# pwm-logger.net
KiCad netlist of a schematic drawn in EAGLE
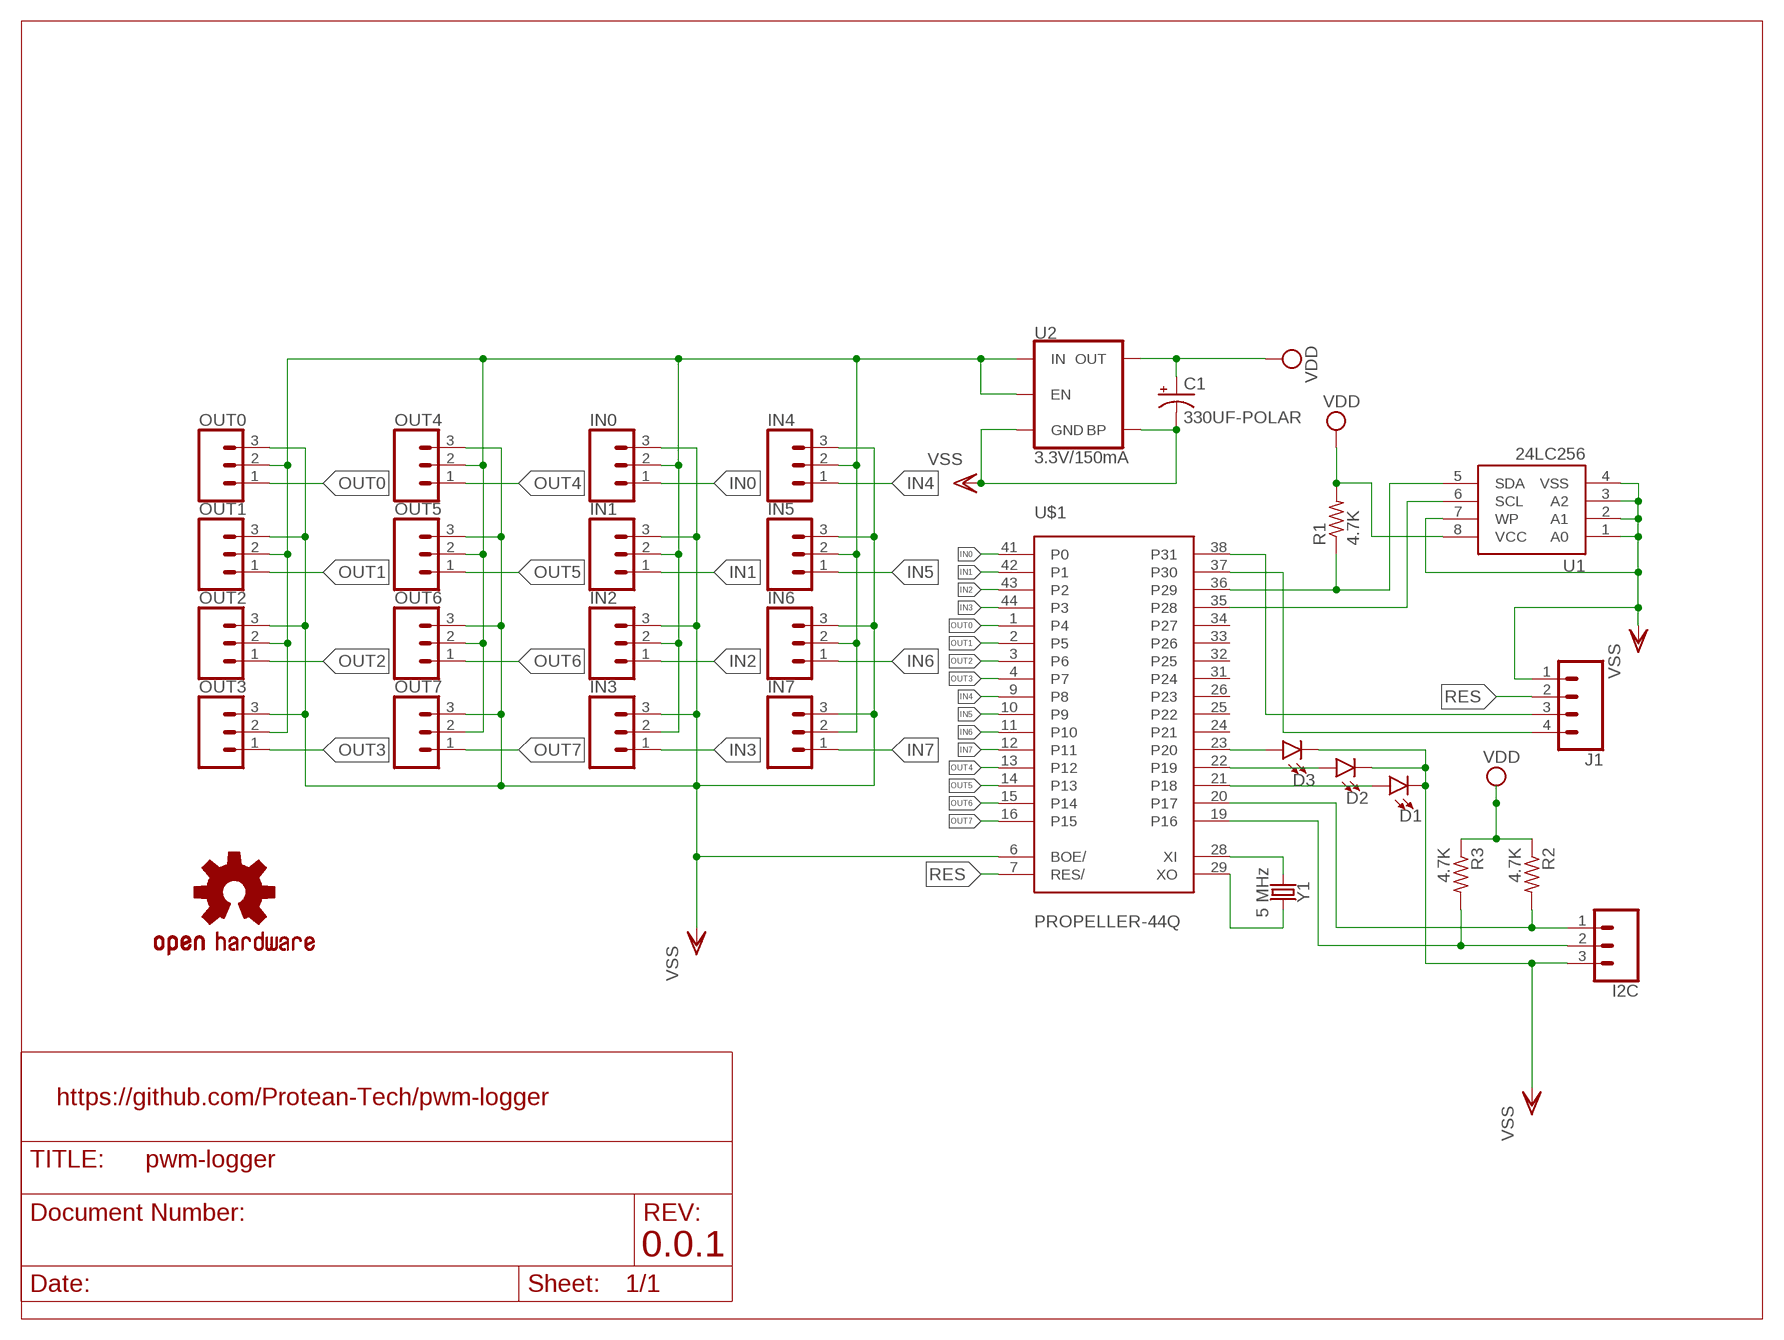
[diagram p0: schematic, sheet 1]

(export (version "E")
  (design (tool "Eeschema 10.0.6"))
  (components
    (comp (ref "C1")
      (value "330UF-POLAR")
      (footprint "eagle-import:1311")
      (libsource (lib "eagle-import") (part "330UF-POLAR"))
    )
    (comp (ref "D1")
      (value "LED-FKIT-1206")
      (footprint "eagle-import:FKIT-LED-1206")
      (libsource (lib "eagle-import") (part "LED-FKIT-1206"))
    )
    (comp (ref "D2")
      (value "LED-FKIT-1206")
      (footprint "eagle-import:FKIT-LED-1206")
      (libsource (lib "eagle-import") (part "LED-FKIT-1206"))
    )
    (comp (ref "D3")
      (value "LED-FKIT-1206")
      (footprint "eagle-import:FKIT-LED-1206")
      (libsource (lib "eagle-import") (part "LED-FKIT-1206"))
    )
    (comp (ref "I2C")
      (value "CONN_03")
      (footprint "eagle-import:1X03")
      (libsource (lib "eagle-import") (part "CONN_03"))
    )
    (comp (ref "IN0")
      (value "CONN_03")
      (footprint "eagle-import:1X03")
      (libsource (lib "eagle-import") (part "CONN_03"))
    )
    (comp (ref "IN1")
      (value "CONN_03")
      (footprint "eagle-import:1X03")
      (libsource (lib "eagle-import") (part "CONN_03"))
    )
    (comp (ref "IN2")
      (value "CONN_03")
      (footprint "eagle-import:1X03")
      (libsource (lib "eagle-import") (part "CONN_03"))
    )
    (comp (ref "IN3")
      (value "CONN_03")
      (footprint "eagle-import:1X03")
      (libsource (lib "eagle-import") (part "CONN_03"))
    )
    (comp (ref "IN4")
      (value "CONN_03")
      (footprint "eagle-import:1X03")
      (libsource (lib "eagle-import") (part "CONN_03"))
    )
    (comp (ref "IN5")
      (value "CONN_03")
      (footprint "eagle-import:1X03")
      (libsource (lib "eagle-import") (part "CONN_03"))
    )
    (comp (ref "IN6")
      (value "CONN_03")
      (footprint "eagle-import:1X03")
      (libsource (lib "eagle-import") (part "CONN_03"))
    )
    (comp (ref "IN7")
      (value "CONN_03")
      (footprint "eagle-import:1X03")
      (libsource (lib "eagle-import") (part "CONN_03"))
    )
    (comp (ref "J1")
      (value "CONN_04")
      (footprint "eagle-import:1X04")
      (libsource (lib "eagle-import") (part "CONN_04"))
    )
    (comp (ref "LOGO1")
      (value "OSHW-LOGOM")
      (footprint "eagle-import:OSHW-LOGO-M")
      (libsource (lib "eagle-import") (part "OSHW-LOGOM"))
    )
    (comp (ref "OUT0")
      (value "CONN_03")
      (footprint "eagle-import:1X03")
      (libsource (lib "eagle-import") (part "CONN_03"))
    )
    (comp (ref "OUT1")
      (value "CONN_03")
      (footprint "eagle-import:1X03")
      (libsource (lib "eagle-import") (part "CONN_03"))
    )
    (comp (ref "OUT2")
      (value "CONN_03")
      (footprint "eagle-import:1X03")
      (libsource (lib "eagle-import") (part "CONN_03"))
    )
    (comp (ref "OUT3")
      (value "CONN_03")
      (footprint "eagle-import:1X03")
      (libsource (lib "eagle-import") (part "CONN_03"))
    )
    (comp (ref "OUT4")
      (value "CONN_03")
      (footprint "eagle-import:1X03")
      (libsource (lib "eagle-import") (part "CONN_03"))
    )
    (comp (ref "OUT5")
      (value "CONN_03")
      (footprint "eagle-import:1X03")
      (libsource (lib "eagle-import") (part "CONN_03"))
    )
    (comp (ref "OUT6")
      (value "CONN_03")
      (footprint "eagle-import:1X03")
      (libsource (lib "eagle-import") (part "CONN_03"))
    )
    (comp (ref "OUT7")
      (value "CONN_03")
      (footprint "eagle-import:1X03")
      (libsource (lib "eagle-import") (part "CONN_03"))
    )
    (comp (ref "R1")
      (value "4.7K")
      (footprint "eagle-import:M2012")
      (libsource (lib "eagle-import") (part "R-US_M2012"))
    )
    (comp (ref "R2")
      (value "4.7K")
      (footprint "eagle-import:M2012")
      (libsource (lib "eagle-import") (part "R-US_M2012"))
    )
    (comp (ref "R3")
      (value "4.7K")
      (footprint "eagle-import:M2012")
      (libsource (lib "eagle-import") (part "R-US_M2012"))
    )
    (comp (ref "U$1")
      (value "PROPELLER-44Q")
      (footprint "eagle-import:Q44")
      (libsource (lib "eagle-import") (part "PROPELLER-44Q"))
    )
    (comp (ref "U1")
      (value "24LC256")
      (footprint "eagle-import:SO08")
      (libsource (lib "eagle-import") (part "EEPROM-I2CSMD"))
    )
    (comp (ref "U2")
      (value "3.3V/150mA")
      (footprint "eagle-import:SOT23-5")
      (libsource (lib "eagle-import") (part "V_REG_MIC52053.3V"))
    )
    (comp (ref "Y1")
      (value "5 MHz")
      (footprint "eagle-import:HC49U")
      (libsource (lib "eagle-import") (part "CRYSTALPTH-HC49UV"))
    )
  )
  (nets
    (net (code "1") (name "IN0") (class "Default")
      (node (ref "IN0") (pin "1") (pinfunction "1_1") (pintype "passive"))
      (node (ref "U$1") (pin "41") (pinfunction "P0_41") (pintype "bidirectional"))
    )
    (net (code "2") (name "IN1") (class "Default")
      (node (ref "IN1") (pin "1") (pinfunction "1_1") (pintype "passive"))
      (node (ref "U$1") (pin "42") (pinfunction "P1_42") (pintype "bidirectional"))
    )
    (net (code "3") (name "IN2") (class "Default")
      (node (ref "IN2") (pin "1") (pinfunction "1_1") (pintype "passive"))
      (node (ref "U$1") (pin "43") (pinfunction "P2_43") (pintype "bidirectional"))
    )
    (net (code "4") (name "IN3") (class "Default")
      (node (ref "IN3") (pin "1") (pinfunction "1_1") (pintype "passive"))
      (node (ref "U$1") (pin "44") (pinfunction "P3_44") (pintype "bidirectional"))
    )
    (net (code "5") (name "IN4") (class "Default")
      (node (ref "IN4") (pin "1") (pinfunction "1_1") (pintype "passive"))
      (node (ref "U$1") (pin "9") (pinfunction "P8_9") (pintype "bidirectional"))
    )
    (net (code "6") (name "IN5") (class "Default")
      (node (ref "IN5") (pin "1") (pinfunction "1_1") (pintype "passive"))
      (node (ref "U$1") (pin "10") (pinfunction "P9_10") (pintype "bidirectional"))
    )
    (net (code "7") (name "IN6") (class "Default")
      (node (ref "IN6") (pin "1") (pinfunction "1_1") (pintype "passive"))
      (node (ref "U$1") (pin "11") (pinfunction "P10_11") (pintype "bidirectional"))
    )
    (net (code "8") (name "IN7") (class "Default")
      (node (ref "IN7") (pin "1") (pinfunction "1_1") (pintype "passive"))
      (node (ref "U$1") (pin "12") (pinfunction "P11_12") (pintype "bidirectional"))
    )
    (net (code "9") (name "Net-(U$1A-P16)") (class "Default")
      (node (ref "I2C") (pin "2") (pinfunction "2_2") (pintype "passive"))
      (node (ref "R3") (pin "2") (pinfunction "2_2") (pintype "passive"))
      (node (ref "U$1") (pin "19") (pinfunction "P16_19") (pintype "bidirectional"))
    )
    (net (code "10") (name "Net-(U$1A-P17)") (class "Default")
      (node (ref "I2C") (pin "1") (pinfunction "1_1") (pintype "passive"))
      (node (ref "R2") (pin "2") (pinfunction "2_2") (pintype "passive"))
      (node (ref "U$1") (pin "20") (pinfunction "P17_20") (pintype "bidirectional"))
    )
    (net (code "11") (name "Net-(U$1A-P18)") (class "Default")
      (node (ref "D1") (pin "A") (pinfunction "A_A") (pintype "passive"))
      (node (ref "U$1") (pin "21") (pinfunction "P18_21") (pintype "bidirectional"))
    )
    (net (code "12") (name "Net-(U$1A-P19)") (class "Default")
      (node (ref "D2") (pin "A") (pinfunction "A_A") (pintype "passive"))
      (node (ref "U$1") (pin "22") (pinfunction "P19_22") (pintype "bidirectional"))
    )
    (net (code "13") (name "Net-(U$1A-P20)") (class "Default")
      (node (ref "D3") (pin "A") (pinfunction "A_A") (pintype "passive"))
      (node (ref "U$1") (pin "23") (pinfunction "P20_23") (pintype "bidirectional"))
    )
    (net (code "14") (name "Net-(U$1A-P28)") (class "Default")
      (node (ref "U$1") (pin "35") (pinfunction "P28_35") (pintype "bidirectional"))
      (node (ref "U1") (pin "6") (pinfunction "SCL_6") (pintype "bidirectional"))
    )
    (net (code "15") (name "Net-(U$1A-P29)") (class "Default")
      (node (ref "R1") (pin "1") (pinfunction "1_1") (pintype "passive"))
      (node (ref "U$1") (pin "36") (pinfunction "P29_36") (pintype "bidirectional"))
      (node (ref "U1") (pin "5") (pinfunction "SDA_5") (pintype "bidirectional"))
    )
    (net (code "16") (name "Net-(U$1A-P30)") (class "Default")
      (node (ref "J1") (pin "4") (pinfunction "4_4") (pintype "passive"))
      (node (ref "U$1") (pin "37") (pinfunction "P30_37") (pintype "bidirectional"))
    )
    (net (code "17") (name "Net-(U$1A-P31)") (class "Default")
      (node (ref "J1") (pin "3") (pinfunction "3_3") (pintype "passive"))
      (node (ref "U$1") (pin "38") (pinfunction "P31_38") (pintype "bidirectional"))
    )
    (net (code "18") (name "Net-(U$1A-XI)") (class "Default")
      (node (ref "U$1") (pin "28") (pinfunction "XI_28") (pintype "input"))
      (node (ref "Y1") (pin "1") (pinfunction "1_1") (pintype "passive"))
    )
    (net (code "19") (name "Net-(U$1A-XO)") (class "Default")
      (node (ref "U$1") (pin "29") (pinfunction "XO_29") (pintype "output"))
      (node (ref "Y1") (pin "2") (pinfunction "2_2") (pintype "passive"))
    )
    (net (code "20") (name "Net-(U2-EN)") (class "Default")
      (node (ref "IN0") (pin "2") (pinfunction "2_2") (pintype "passive"))
      (node (ref "IN1") (pin "2") (pinfunction "2_2") (pintype "passive"))
      (node (ref "IN2") (pin "2") (pinfunction "2_2") (pintype "passive"))
      (node (ref "IN3") (pin "2") (pinfunction "2_2") (pintype "passive"))
      (node (ref "IN4") (pin "2") (pinfunction "2_2") (pintype "passive"))
      (node (ref "IN5") (pin "2") (pinfunction "2_2") (pintype "passive"))
      (node (ref "IN6") (pin "2") (pinfunction "2_2") (pintype "passive"))
      (node (ref "IN7") (pin "2") (pinfunction "2_2") (pintype "passive"))
      (node (ref "OUT0") (pin "2") (pinfunction "2_2") (pintype "passive"))
      (node (ref "OUT1") (pin "2") (pinfunction "2_2") (pintype "passive"))
      (node (ref "OUT2") (pin "2") (pinfunction "2_2") (pintype "passive"))
      (node (ref "OUT3") (pin "2") (pinfunction "2_2") (pintype "passive"))
      (node (ref "OUT4") (pin "2") (pinfunction "2_2") (pintype "passive"))
      (node (ref "OUT5") (pin "2") (pinfunction "2_2") (pintype "passive"))
      (node (ref "OUT6") (pin "2") (pinfunction "2_2") (pintype "passive"))
      (node (ref "OUT7") (pin "2") (pinfunction "2_2") (pintype "passive"))
      (node (ref "U2") (pin "1") (pinfunction "IN_1") (pintype "input"))
      (node (ref "U2") (pin "3") (pinfunction "EN_3") (pintype "input"))
    )
    (net (code "21") (name "OUT0") (class "Default")
      (node (ref "OUT0") (pin "1") (pinfunction "1_1") (pintype "passive"))
      (node (ref "U$1") (pin "1") (pinfunction "P4_1") (pintype "bidirectional"))
    )
    (net (code "22") (name "OUT1") (class "Default")
      (node (ref "OUT1") (pin "1") (pinfunction "1_1") (pintype "passive"))
      (node (ref "U$1") (pin "2") (pinfunction "P5_2") (pintype "bidirectional"))
    )
    (net (code "23") (name "OUT2") (class "Default")
      (node (ref "OUT2") (pin "1") (pinfunction "1_1") (pintype "passive"))
      (node (ref "U$1") (pin "3") (pinfunction "P6_3") (pintype "bidirectional"))
    )
    (net (code "24") (name "OUT3") (class "Default")
      (node (ref "OUT3") (pin "1") (pinfunction "1_1") (pintype "passive"))
      (node (ref "U$1") (pin "4") (pinfunction "P7_4") (pintype "bidirectional"))
    )
    (net (code "25") (name "OUT4") (class "Default")
      (node (ref "OUT4") (pin "1") (pinfunction "1_1") (pintype "passive"))
      (node (ref "U$1") (pin "13") (pinfunction "P12_13") (pintype "bidirectional"))
    )
    (net (code "26") (name "OUT5") (class "Default")
      (node (ref "OUT5") (pin "1") (pinfunction "1_1") (pintype "passive"))
      (node (ref "U$1") (pin "14") (pinfunction "P13_14") (pintype "bidirectional"))
    )
    (net (code "27") (name "OUT6") (class "Default")
      (node (ref "OUT6") (pin "1") (pinfunction "1_1") (pintype "passive"))
      (node (ref "U$1") (pin "15") (pinfunction "P14_15") (pintype "bidirectional"))
    )
    (net (code "28") (name "OUT7") (class "Default")
      (node (ref "OUT7") (pin "1") (pinfunction "1_1") (pintype "passive"))
      (node (ref "U$1") (pin "16") (pinfunction "P15_16") (pintype "bidirectional"))
    )
    (net (code "29") (name "RES") (class "Default")
      (node (ref "J1") (pin "2") (pinfunction "2_2") (pintype "passive"))
      (node (ref "U$1") (pin "7") (pinfunction "RES/_7") (pintype "bidirectional"))
    )
    (net (code "30") (name "VDD") (class "Default")
      (node (ref "C1") (pin "+") (pinfunction "+_+") (pintype "passive"))
      (node (ref "R1") (pin "2") (pinfunction "2_2") (pintype "passive"))
      (node (ref "R2") (pin "1") (pinfunction "1_1") (pintype "passive"))
      (node (ref "R3") (pin "1") (pinfunction "1_1") (pintype "passive"))
      (node (ref "U1") (pin "8") (pinfunction "VCC_8") (pintype "power_in"))
      (node (ref "U2") (pin "5") (pinfunction "OUT_5") (pintype "passive"))
    )
    (net (code "31") (name "VSS") (class "Default")
      (node (ref "C1") (pin "-") (pinfunction "-_-") (pintype "passive"))
      (node (ref "D1") (pin "C") (pinfunction "C_C") (pintype "passive"))
      (node (ref "D2") (pin "C") (pinfunction "C_C") (pintype "passive"))
      (node (ref "D3") (pin "C") (pinfunction "C_C") (pintype "passive"))
      (node (ref "I2C") (pin "3") (pinfunction "3_3") (pintype "passive"))
      (node (ref "IN0") (pin "3") (pinfunction "3_3") (pintype "passive"))
      (node (ref "IN1") (pin "3") (pinfunction "3_3") (pintype "passive"))
      (node (ref "IN2") (pin "3") (pinfunction "3_3") (pintype "passive"))
      (node (ref "IN3") (pin "3") (pinfunction "3_3") (pintype "passive"))
      (node (ref "IN4") (pin "3") (pinfunction "3_3") (pintype "passive"))
      (node (ref "IN5") (pin "3") (pinfunction "3_3") (pintype "passive"))
      (node (ref "IN6") (pin "3") (pinfunction "3_3") (pintype "passive"))
      (node (ref "IN7") (pin "3") (pinfunction "3_3") (pintype "passive"))
      (node (ref "J1") (pin "1") (pinfunction "1_1") (pintype "passive"))
      (node (ref "OUT0") (pin "3") (pinfunction "3_3") (pintype "passive"))
      (node (ref "OUT1") (pin "3") (pinfunction "3_3") (pintype "passive"))
      (node (ref "OUT2") (pin "3") (pinfunction "3_3") (pintype "passive"))
      (node (ref "OUT3") (pin "3") (pinfunction "3_3") (pintype "passive"))
      (node (ref "OUT4") (pin "3") (pinfunction "3_3") (pintype "passive"))
      (node (ref "OUT5") (pin "3") (pinfunction "3_3") (pintype "passive"))
      (node (ref "OUT6") (pin "3") (pinfunction "3_3") (pintype "passive"))
      (node (ref "OUT7") (pin "3") (pinfunction "3_3") (pintype "passive"))
      (node (ref "U$1") (pin "6") (pinfunction "BOE/_6") (pintype "input"))
      (node (ref "U1") (pin "1") (pinfunction "A0_1") (pintype "bidirectional"))
      (node (ref "U1") (pin "2") (pinfunction "A1_2") (pintype "bidirectional"))
      (node (ref "U1") (pin "3") (pinfunction "A2_3") (pintype "bidirectional"))
      (node (ref "U1") (pin "4") (pinfunction "VSS_4") (pintype "power_in"))
      (node (ref "U1") (pin "7") (pinfunction "WP_7") (pintype "bidirectional"))
      (node (ref "U2") (pin "2") (pinfunction "GND_2") (pintype "input"))
      (node (ref "U2") (pin "4") (pinfunction "BP_4") (pintype "input"))
    )
    (net (code "32") (name "unconnected-(U$1A-P21-Pad24)") (class "Default")
      (node (ref "U$1") (pin "24") (pinfunction "P21_24") (pintype "bidirectional"))
    )
    (net (code "33") (name "unconnected-(U$1A-P22-Pad25)") (class "Default")
      (node (ref "U$1") (pin "25") (pinfunction "P22_25") (pintype "bidirectional"))
    )
    (net (code "34") (name "unconnected-(U$1A-P23-Pad26)") (class "Default")
      (node (ref "U$1") (pin "26") (pinfunction "P23_26") (pintype "bidirectional"))
    )
    (net (code "35") (name "unconnected-(U$1A-P24-Pad31)") (class "Default")
      (node (ref "U$1") (pin "31") (pinfunction "P24_31") (pintype "bidirectional"))
    )
    (net (code "36") (name "unconnected-(U$1A-P25-Pad32)") (class "Default")
      (node (ref "U$1") (pin "32") (pinfunction "P25_32") (pintype "bidirectional"))
    )
    (net (code "37") (name "unconnected-(U$1A-P26-Pad33)") (class "Default")
      (node (ref "U$1") (pin "33") (pinfunction "P26_33") (pintype "bidirectional"))
    )
    (net (code "38") (name "unconnected-(U$1A-P27-Pad34)") (class "Default")
      (node (ref "U$1") (pin "34") (pinfunction "P27_34") (pintype "bidirectional"))
    )
  )
)
